# schematic.net
KiCad netlist of a schematic drawn in EasyEDA
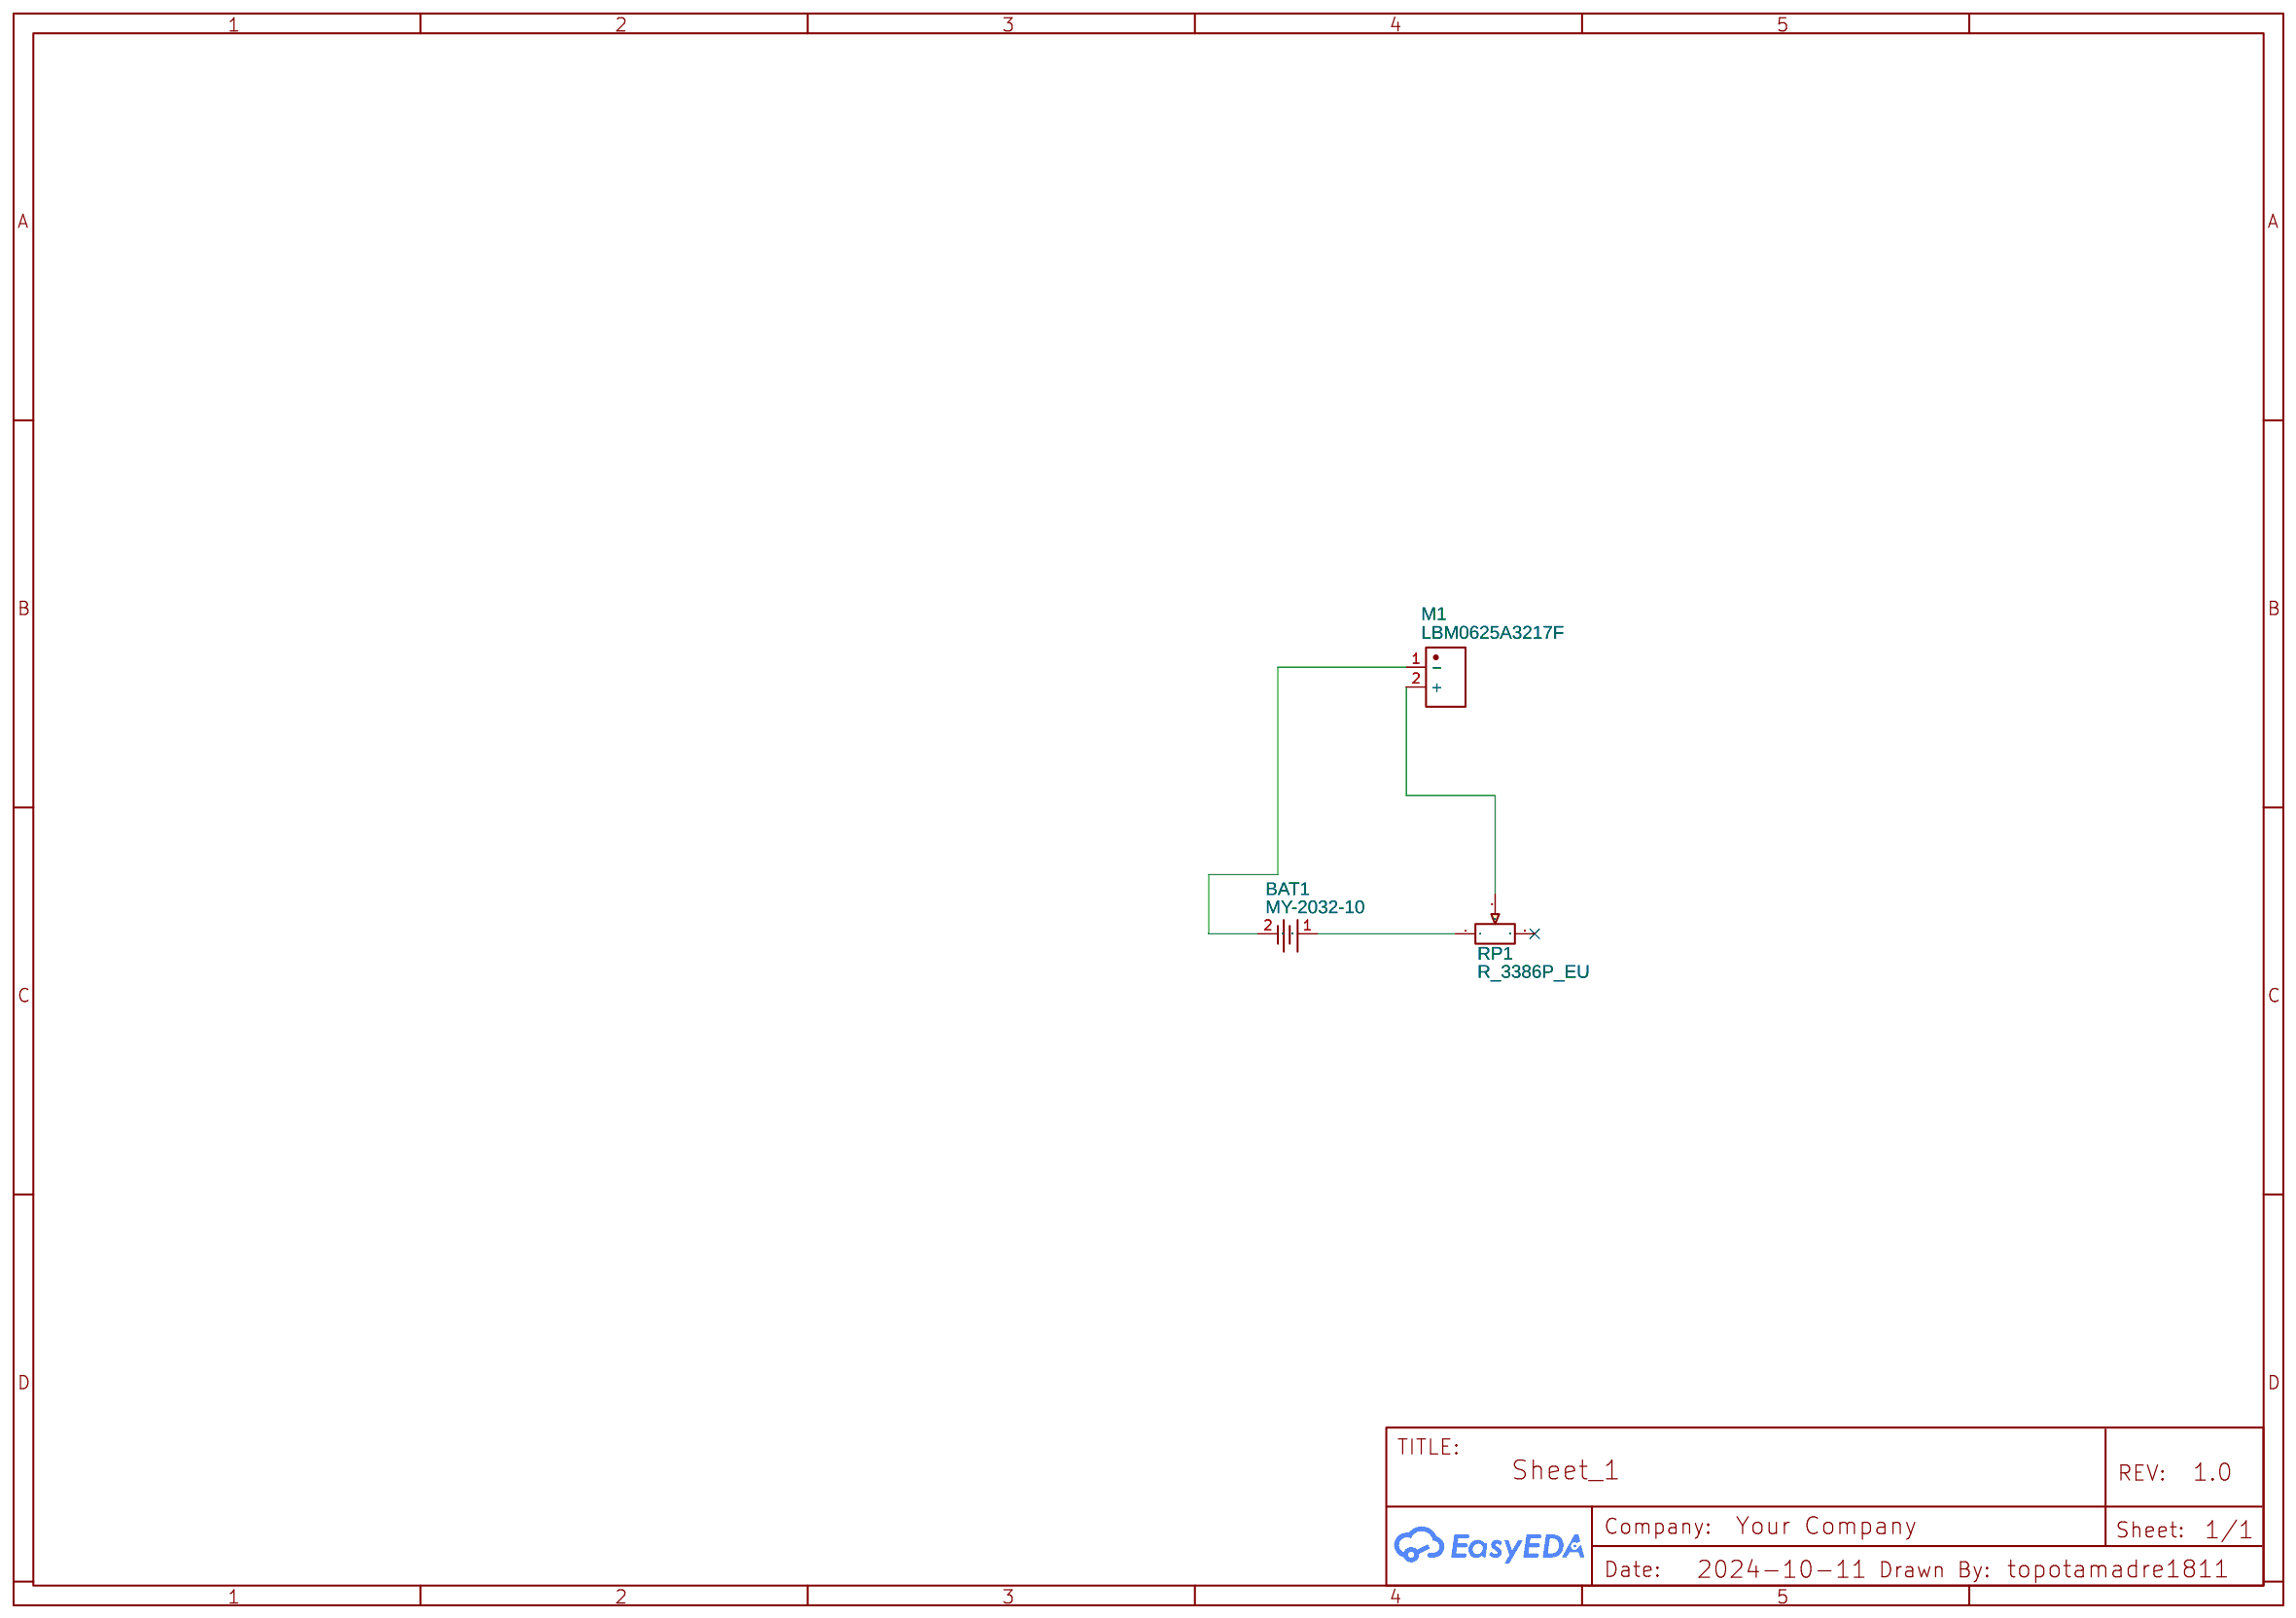
[diagram p0: schematic sheet]

(export (version "E")
  (design (tool "Eeschema 10.0.6"))
  (components
    (comp (ref "BAT1")
      (value "MY-2032-10")
      (fields (field (name "Manufacturer") "MYOUNG(美阳)"))
      (libsource (lib "") (part "MY-2032-10"))
    )
    (comp (ref "M1")
      (value "LBM0625A3217F")
      (fields (field (name "Manufacturer") "LEADER(立得)"))
      (libsource (lib "") (part "LBM0625A3217F"))
    )
    (comp (ref "RP1") (value "R_3386P_EU") (libsource (lib "") (part "R_3386P_EU")))
  )
  (nets
    (net (code "1") (name "Net-(BAT1-BAT+)") (class "Default")
      (node (ref "BAT1") (pin "1") (pinfunction "BAT+_1") (pintype "input"))
      (node (ref "RP1") (pin "1") (pinfunction "1_1") (pintype "input"))
    )
    (net (code "2") (name "Net-(BAT1-BAT-)") (class "Default")
      (node (ref "BAT1") (pin "2") (pinfunction "BAT-_2") (pintype "input"))
      (node (ref "M1") (pin "1") (pinfunction "-_1") (pintype "unspecified"))
    )
    (net (code "3") (name "Net-(M1-+)") (class "Default")
      (node (ref "M1") (pin "2") (pinfunction "+_2") (pintype "unspecified"))
      (node (ref "RP1") (pin "2") (pinfunction "2_2") (pintype "input"))
    )
    (net (code "4") (name "unconnected-(RP1-Pad3)") (class "Default")
      (node (ref "RP1") (pin "3") (pinfunction "3_3") (pintype "input+no_connect"))
    )
  )
)
